# TI1-1-Top.net
KiCad netlist of a schematic drawn in Altium Designer
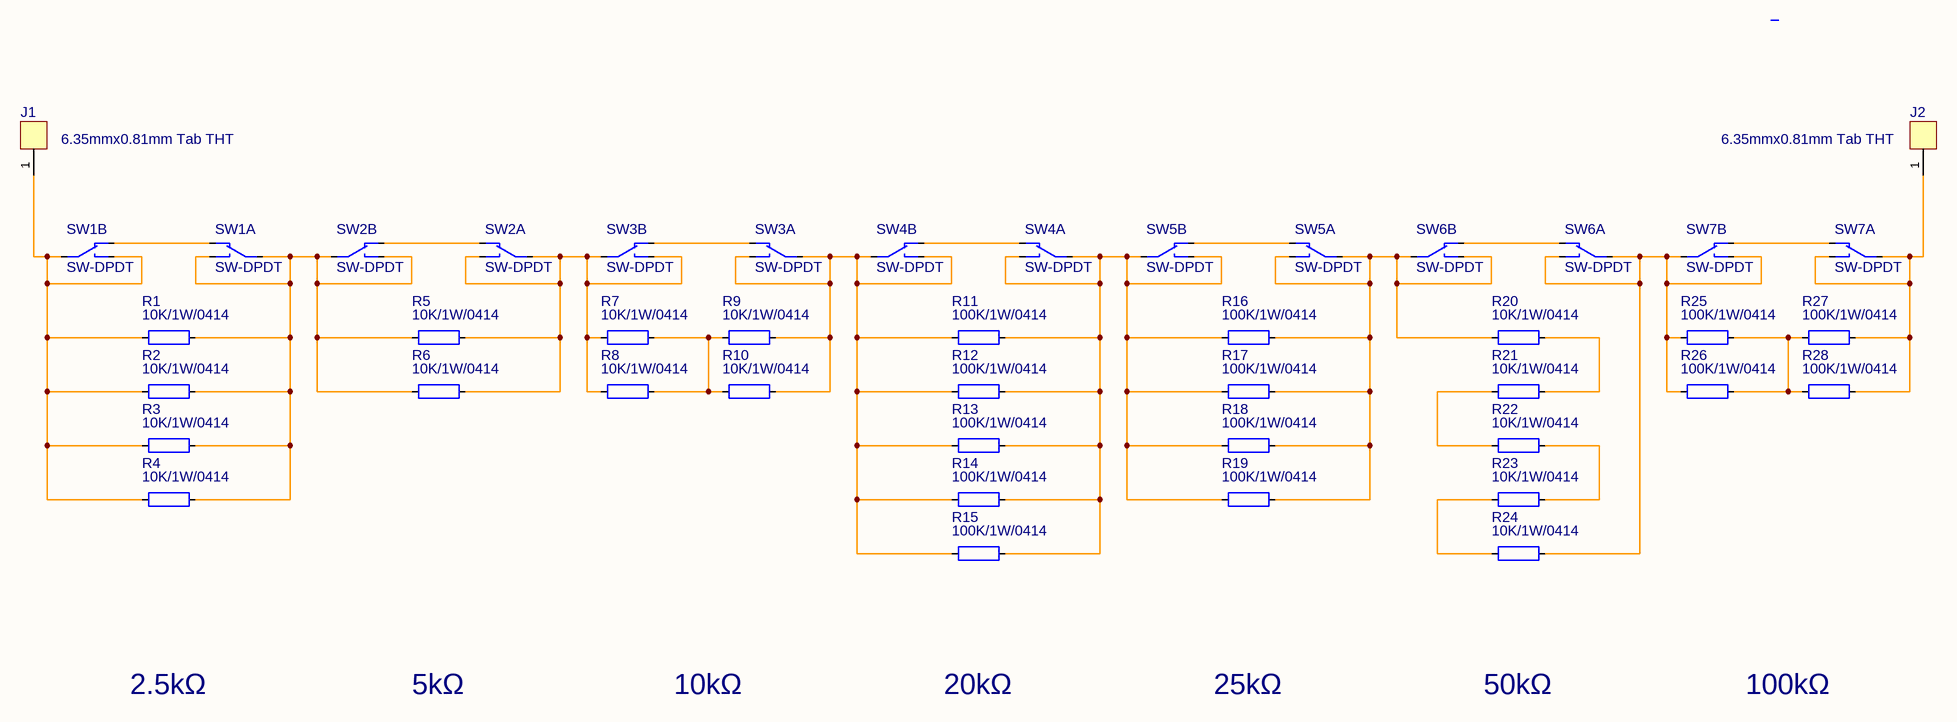
[diagram p0: TI1-1-Top.SchDoc]

(export (version "E")
  (design (tool "Eeschema 10.0.6"))
  (components
    (comp (ref "J1")
      (value "6.35mmx0.81mm Tab THT")
      (footprint "Tab_THT_635")
      (description "CONN QC TAB 0.250 SOLDER")
      (fields (field (name "PART NUMBER") "Tab_025_THT") (field (name "MANUFACTURER") "GENERIC"))
      (libsource (lib "daniw_altium_lib") (part "CON1"))
    )
    (comp (ref "J2")
      (value "6.35mmx0.81mm Tab THT")
      (footprint "Tab_THT_635")
      (description "CONN QC TAB 0.250 SOLDER")
      (fields (field (name "PART NUMBER") "Tab_025_THT") (field (name "MANUFACTURER") "GENERIC"))
      (libsource (lib "daniw_altium_lib") (part "CON1"))
    )
    (comp (ref "R1")
      (value "10K/1W/0414")
      (footprint "RESAD1500W80L1200D400B")
      (description "RES TH 1W 0414 10K")
      (fields (field (name "MANUFACTURER") "GENERIC"))
      (libsource (lib "daniw_altium_lib") (part "R"))
    )
    (comp (ref "R2")
      (value "10K/1W/0414")
      (footprint "RESAD1500W80L1200D400B")
      (description "RES TH 1W 0414 10K")
      (fields (field (name "MANUFACTURER") "GENERIC"))
      (libsource (lib "daniw_altium_lib") (part "R"))
    )
    (comp (ref "R3")
      (value "10K/1W/0414")
      (footprint "RESAD1500W80L1200D400B")
      (description "RES TH 1W 0414 10K")
      (fields (field (name "MANUFACTURER") "GENERIC"))
      (libsource (lib "daniw_altium_lib") (part "R"))
    )
    (comp (ref "R4")
      (value "10K/1W/0414")
      (footprint "RESAD1500W80L1200D400B")
      (description "RES TH 1W 0414 10K")
      (fields (field (name "MANUFACTURER") "GENERIC"))
      (libsource (lib "daniw_altium_lib") (part "R"))
    )
    (comp (ref "R5")
      (value "10K/1W/0414")
      (footprint "RESAD1500W80L1200D400B")
      (description "RES TH 1W 0414 10K")
      (fields (field (name "MANUFACTURER") "GENERIC"))
      (libsource (lib "daniw_altium_lib") (part "R"))
    )
    (comp (ref "R6")
      (value "10K/1W/0414")
      (footprint "RESAD1500W80L1200D400B")
      (description "RES TH 1W 0414 10K")
      (fields (field (name "MANUFACTURER") "GENERIC"))
      (libsource (lib "daniw_altium_lib") (part "R"))
    )
    (comp (ref "R7")
      (value "10K/1W/0414")
      (footprint "RESAD1500W80L1200D400B")
      (description "RES TH 1W 0414 10K")
      (fields (field (name "MANUFACTURER") "GENERIC"))
      (libsource (lib "daniw_altium_lib") (part "R"))
    )
    (comp (ref "R8")
      (value "10K/1W/0414")
      (footprint "RESAD1500W80L1200D400B")
      (description "RES TH 1W 0414 10K")
      (fields (field (name "MANUFACTURER") "GENERIC"))
      (libsource (lib "daniw_altium_lib") (part "R"))
    )
    (comp (ref "R9")
      (value "10K/1W/0414")
      (footprint "RESAD1500W80L1200D400B")
      (description "RES TH 1W 0414 10K")
      (fields (field (name "MANUFACTURER") "GENERIC"))
      (libsource (lib "daniw_altium_lib") (part "R"))
    )
    (comp (ref "R10")
      (value "10K/1W/0414")
      (footprint "RESAD1500W80L1200D400B")
      (description "RES TH 1W 0414 10K")
      (fields (field (name "MANUFACTURER") "GENERIC"))
      (libsource (lib "daniw_altium_lib") (part "R"))
    )
    (comp (ref "R11")
      (value "100K/1W/0414")
      (footprint "RESAD1500W80L1200D400B")
      (description "RES TH 1W 0414 100K")
      (fields (field (name "MANUFACTURER") "GENERIC"))
      (libsource (lib "daniw_altium_lib") (part "R"))
    )
    (comp (ref "R12")
      (value "100K/1W/0414")
      (footprint "RESAD1500W80L1200D400B")
      (description "RES TH 1W 0414 100K")
      (fields (field (name "MANUFACTURER") "GENERIC"))
      (libsource (lib "daniw_altium_lib") (part "R"))
    )
    (comp (ref "R13")
      (value "100K/1W/0414")
      (footprint "RESAD1500W80L1200D400B")
      (description "RES TH 1W 0414 100K")
      (fields (field (name "MANUFACTURER") "GENERIC"))
      (libsource (lib "daniw_altium_lib") (part "R"))
    )
    (comp (ref "R14")
      (value "100K/1W/0414")
      (footprint "RESAD1500W80L1200D400B")
      (description "RES TH 1W 0414 100K")
      (fields (field (name "MANUFACTURER") "GENERIC"))
      (libsource (lib "daniw_altium_lib") (part "R"))
    )
    (comp (ref "R15")
      (value "100K/1W/0414")
      (footprint "RESAD1500W80L1200D400B")
      (description "RES TH 1W 0414 100K")
      (fields (field (name "MANUFACTURER") "GENERIC"))
      (libsource (lib "daniw_altium_lib") (part "R"))
    )
    (comp (ref "R16")
      (value "100K/1W/0414")
      (footprint "RESAD1500W80L1200D400B")
      (description "RES TH 1W 0414 100K")
      (fields (field (name "MANUFACTURER") "GENERIC"))
      (libsource (lib "daniw_altium_lib") (part "R"))
    )
    (comp (ref "R17")
      (value "100K/1W/0414")
      (footprint "RESAD1500W80L1200D400B")
      (description "RES TH 1W 0414 100K")
      (fields (field (name "MANUFACTURER") "GENERIC"))
      (libsource (lib "daniw_altium_lib") (part "R"))
    )
    (comp (ref "R18")
      (value "100K/1W/0414")
      (footprint "RESAD1500W80L1200D400B")
      (description "RES TH 1W 0414 100K")
      (fields (field (name "MANUFACTURER") "GENERIC"))
      (libsource (lib "daniw_altium_lib") (part "R"))
    )
    (comp (ref "R19")
      (value "100K/1W/0414")
      (footprint "RESAD1500W80L1200D400B")
      (description "RES TH 1W 0414 100K")
      (fields (field (name "MANUFACTURER") "GENERIC"))
      (libsource (lib "daniw_altium_lib") (part "R"))
    )
    (comp (ref "R20")
      (value "10K/1W/0414")
      (footprint "RESAD1500W80L1200D400B")
      (description "RES TH 1W 0414 10K")
      (fields (field (name "MANUFACTURER") "GENERIC"))
      (libsource (lib "daniw_altium_lib") (part "R"))
    )
    (comp (ref "R21")
      (value "10K/1W/0414")
      (footprint "RESAD1500W80L1200D400B")
      (description "RES TH 1W 0414 10K")
      (fields (field (name "MANUFACTURER") "GENERIC"))
      (libsource (lib "daniw_altium_lib") (part "R"))
    )
    (comp (ref "R22")
      (value "10K/1W/0414")
      (footprint "RESAD1500W80L1200D400B")
      (description "RES TH 1W 0414 10K")
      (fields (field (name "MANUFACTURER") "GENERIC"))
      (libsource (lib "daniw_altium_lib") (part "R"))
    )
    (comp (ref "R23")
      (value "10K/1W/0414")
      (footprint "RESAD1500W80L1200D400B")
      (description "RES TH 1W 0414 10K")
      (fields (field (name "MANUFACTURER") "GENERIC"))
      (libsource (lib "daniw_altium_lib") (part "R"))
    )
    (comp (ref "R24")
      (value "10K/1W/0414")
      (footprint "RESAD1500W80L1200D400B")
      (description "RES TH 1W 0414 10K")
      (fields (field (name "MANUFACTURER") "GENERIC"))
      (libsource (lib "daniw_altium_lib") (part "R"))
    )
    (comp (ref "R25")
      (value "100K/1W/0414")
      (footprint "RESAD1500W80L1200D400B")
      (description "RES TH 1W 0414 100K")
      (fields (field (name "MANUFACTURER") "GENERIC"))
      (libsource (lib "daniw_altium_lib") (part "R"))
    )
    (comp (ref "R26")
      (value "100K/1W/0414")
      (footprint "RESAD1500W80L1200D400B")
      (description "RES TH 1W 0414 100K")
      (fields (field (name "MANUFACTURER") "GENERIC"))
      (libsource (lib "daniw_altium_lib") (part "R"))
    )
    (comp (ref "R27")
      (value "100K/1W/0414")
      (footprint "RESAD1500W80L1200D400B")
      (description "RES TH 1W 0414 100K")
      (fields (field (name "MANUFACTURER") "GENERIC"))
      (libsource (lib "daniw_altium_lib") (part "R"))
    )
    (comp (ref "R28")
      (value "100K/1W/0414")
      (footprint "RESAD1500W80L1200D400B")
      (description "RES TH 1W 0414 100K")
      (fields (field (name "MANUFACTURER") "GENERIC"))
      (libsource (lib "daniw_altium_lib") (part "R"))
    )
    (comp (ref "SW1")
      (value "SW-DPDT")
      (footprint "RND_DPDT_12.6mm_210-00450")
      (description "Miniature Toggle Switch, ON-ON, DPDT, 2A, IP67")
      (fields (field (name "PART NUMBER") "SW-DPDT-RND-210-00450") (field (name "MANUFACTURER") "RND"))
      (libsource (lib "daniw_altium_lib") (part "SW_DPDT"))
    )
    (comp (ref "SW2")
      (value "SW-DPDT")
      (footprint "RND_DPDT_12.6mm_210-00450")
      (description "Miniature Toggle Switch, ON-ON, DPDT, 2A, IP67")
      (fields (field (name "PART NUMBER") "SW-DPDT-RND-210-00450") (field (name "MANUFACTURER") "RND"))
      (libsource (lib "daniw_altium_lib") (part "SW_DPDT"))
    )
    (comp (ref "SW3")
      (value "SW-DPDT")
      (footprint "RND_DPDT_12.6mm_210-00450")
      (description "Miniature Toggle Switch, ON-ON, DPDT, 2A, IP67")
      (fields (field (name "PART NUMBER") "SW-DPDT-RND-210-00450") (field (name "MANUFACTURER") "RND"))
      (libsource (lib "daniw_altium_lib") (part "SW_DPDT"))
    )
    (comp (ref "SW4")
      (value "SW-DPDT")
      (footprint "RND_DPDT_12.6mm_210-00450")
      (description "Miniature Toggle Switch, ON-ON, DPDT, 2A, IP67")
      (fields (field (name "PART NUMBER") "SW-DPDT-RND-210-00450") (field (name "MANUFACTURER") "RND"))
      (libsource (lib "daniw_altium_lib") (part "SW_DPDT"))
    )
    (comp (ref "SW5")
      (value "SW-DPDT")
      (footprint "RND_DPDT_12.6mm_210-00450")
      (description "Miniature Toggle Switch, ON-ON, DPDT, 2A, IP67")
      (fields (field (name "PART NUMBER") "SW-DPDT-RND-210-00450") (field (name "MANUFACTURER") "RND"))
      (libsource (lib "daniw_altium_lib") (part "SW_DPDT"))
    )
    (comp (ref "SW6")
      (value "SW-DPDT")
      (footprint "RND_DPDT_12.6mm_210-00450")
      (description "Miniature Toggle Switch, ON-ON, DPDT, 2A, IP67")
      (fields (field (name "PART NUMBER") "SW-DPDT-RND-210-00450") (field (name "MANUFACTURER") "RND"))
      (libsource (lib "daniw_altium_lib") (part "SW_DPDT"))
    )
    (comp (ref "SW7")
      (value "SW-DPDT")
      (footprint "RND_DPDT_12.6mm_210-00450")
      (description "Miniature Toggle Switch, ON-ON, DPDT, 2A, IP67")
      (fields (field (name "PART NUMBER") "SW-DPDT-RND-210-00450") (field (name "MANUFACTURER") "RND"))
      (libsource (lib "daniw_altium_lib") (part "SW_DPDT"))
    )
  )
  (nets
    (net (code "1") (name "Net-(R10-Pad2)") (class "Default")
      (node (ref "R10") (pin "2") (pinfunction "2_2") (pintype "passive"))
      (node (ref "R7") (pin "1") (pinfunction "1_1") (pintype "passive"))
      (node (ref "R8") (pin "1") (pinfunction "1_1") (pintype "passive"))
      (node (ref "R9") (pin "2") (pinfunction "2_2") (pintype "passive"))
    )
    (net (code "2") (name "Net-(R20-Pad1)") (class "Default")
      (node (ref "R20") (pin "1") (pinfunction "1_1") (pintype "passive"))
      (node (ref "R21") (pin "1") (pinfunction "1_1") (pintype "passive"))
    )
    (net (code "3") (name "Net-(R21-Pad2)") (class "Default")
      (node (ref "R21") (pin "2") (pinfunction "2_2") (pintype "passive"))
      (node (ref "R22") (pin "2") (pinfunction "2_2") (pintype "passive"))
    )
    (net (code "4") (name "Net-(R22-Pad1)") (class "Default")
      (node (ref "R22") (pin "1") (pinfunction "1_1") (pintype "passive"))
      (node (ref "R23") (pin "1") (pinfunction "1_1") (pintype "passive"))
    )
    (net (code "5") (name "Net-(R23-Pad2)") (class "Default")
      (node (ref "R23") (pin "2") (pinfunction "2_2") (pintype "passive"))
      (node (ref "R24") (pin "2") (pinfunction "2_2") (pintype "passive"))
    )
    (net (code "6") (name "Net-(R25-Pad1)") (class "Default")
      (node (ref "R25") (pin "1") (pinfunction "1_1") (pintype "passive"))
      (node (ref "R26") (pin "1") (pinfunction "1_1") (pintype "passive"))
      (node (ref "R27") (pin "2") (pinfunction "2_2") (pintype "passive"))
      (node (ref "R28") (pin "2") (pinfunction "2_2") (pintype "passive"))
    )
    (net (code "7") (name "Net-(SW1A-COM1)") (class "Default")
      (node (ref "R1") (pin "1") (pinfunction "1_1") (pintype "passive"))
      (node (ref "R2") (pin "1") (pinfunction "1_1") (pintype "passive"))
      (node (ref "R3") (pin "1") (pinfunction "1_1") (pintype "passive"))
      (node (ref "R4") (pin "1") (pinfunction "1_1") (pintype "passive"))
      (node (ref "R5") (pin "2") (pinfunction "2_2") (pintype "passive"))
      (node (ref "R6") (pin "2") (pinfunction "2_2") (pintype "passive"))
      (node (ref "SW1") (pin "1") (pinfunction "COM1_1") (pintype "passive"))
      (node (ref "SW1") (pin "3") (pinfunction "NO1_3") (pintype "passive"))
      (node (ref "SW2") (pin "4") (pinfunction "COM2_4") (pintype "passive"))
      (node (ref "SW2") (pin "6") (pinfunction "NO2_6") (pintype "passive"))
    )
    (net (code "8") (name "Net-(SW1A-NC1)") (class "Default")
      (node (ref "SW1") (pin "2") (pinfunction "NC1_2") (pintype "passive"))
      (node (ref "SW1") (pin "5") (pinfunction "NC2_5") (pintype "passive"))
    )
    (net (code "9") (name "Net-(SW1B-COM2)") (class "Default")
      (node (ref "J1") (pin "1") (pintype "passive"))
      (node (ref "R1") (pin "2") (pinfunction "2_2") (pintype "passive"))
      (node (ref "R2") (pin "2") (pinfunction "2_2") (pintype "passive"))
      (node (ref "R3") (pin "2") (pinfunction "2_2") (pintype "passive"))
      (node (ref "R4") (pin "2") (pinfunction "2_2") (pintype "passive"))
      (node (ref "SW1") (pin "4") (pinfunction "COM2_4") (pintype "passive"))
      (node (ref "SW1") (pin "6") (pinfunction "NO2_6") (pintype "passive"))
    )
    (net (code "10") (name "Net-(SW2A-COM1)") (class "Default")
      (node (ref "R5") (pin "1") (pinfunction "1_1") (pintype "passive"))
      (node (ref "R6") (pin "1") (pinfunction "1_1") (pintype "passive"))
      (node (ref "R7") (pin "2") (pinfunction "2_2") (pintype "passive"))
      (node (ref "R8") (pin "2") (pinfunction "2_2") (pintype "passive"))
      (node (ref "SW2") (pin "1") (pinfunction "COM1_1") (pintype "passive"))
      (node (ref "SW2") (pin "3") (pinfunction "NO1_3") (pintype "passive"))
      (node (ref "SW3") (pin "4") (pinfunction "COM2_4") (pintype "passive"))
      (node (ref "SW3") (pin "6") (pinfunction "NO2_6") (pintype "passive"))
    )
    (net (code "11") (name "Net-(SW2A-NC1)") (class "Default")
      (node (ref "SW2") (pin "2") (pinfunction "NC1_2") (pintype "passive"))
      (node (ref "SW2") (pin "5") (pinfunction "NC2_5") (pintype "passive"))
    )
    (net (code "12") (name "Net-(SW3A-COM1)") (class "Default")
      (node (ref "R10") (pin "1") (pinfunction "1_1") (pintype "passive"))
      (node (ref "R11") (pin "2") (pinfunction "2_2") (pintype "passive"))
      (node (ref "R12") (pin "2") (pinfunction "2_2") (pintype "passive"))
      (node (ref "R13") (pin "2") (pinfunction "2_2") (pintype "passive"))
      (node (ref "R14") (pin "2") (pinfunction "2_2") (pintype "passive"))
      (node (ref "R15") (pin "2") (pinfunction "2_2") (pintype "passive"))
      (node (ref "R9") (pin "1") (pinfunction "1_1") (pintype "passive"))
      (node (ref "SW3") (pin "1") (pinfunction "COM1_1") (pintype "passive"))
      (node (ref "SW3") (pin "3") (pinfunction "NO1_3") (pintype "passive"))
      (node (ref "SW4") (pin "4") (pinfunction "COM2_4") (pintype "passive"))
      (node (ref "SW4") (pin "6") (pinfunction "NO2_6") (pintype "passive"))
    )
    (net (code "13") (name "Net-(SW3A-NC1)") (class "Default")
      (node (ref "SW3") (pin "2") (pinfunction "NC1_2") (pintype "passive"))
      (node (ref "SW3") (pin "5") (pinfunction "NC2_5") (pintype "passive"))
    )
    (net (code "14") (name "Net-(SW4A-COM1)") (class "Default")
      (node (ref "R11") (pin "1") (pinfunction "1_1") (pintype "passive"))
      (node (ref "R12") (pin "1") (pinfunction "1_1") (pintype "passive"))
      (node (ref "R13") (pin "1") (pinfunction "1_1") (pintype "passive"))
      (node (ref "R14") (pin "1") (pinfunction "1_1") (pintype "passive"))
      (node (ref "R15") (pin "1") (pinfunction "1_1") (pintype "passive"))
      (node (ref "R16") (pin "2") (pinfunction "2_2") (pintype "passive"))
      (node (ref "R17") (pin "2") (pinfunction "2_2") (pintype "passive"))
      (node (ref "R18") (pin "2") (pinfunction "2_2") (pintype "passive"))
      (node (ref "R19") (pin "2") (pinfunction "2_2") (pintype "passive"))
      (node (ref "SW4") (pin "1") (pinfunction "COM1_1") (pintype "passive"))
      (node (ref "SW4") (pin "3") (pinfunction "NO1_3") (pintype "passive"))
      (node (ref "SW5") (pin "4") (pinfunction "COM2_4") (pintype "passive"))
      (node (ref "SW5") (pin "6") (pinfunction "NO2_6") (pintype "passive"))
    )
    (net (code "15") (name "Net-(SW4A-NC1)") (class "Default")
      (node (ref "SW4") (pin "2") (pinfunction "NC1_2") (pintype "passive"))
      (node (ref "SW4") (pin "5") (pinfunction "NC2_5") (pintype "passive"))
    )
    (net (code "16") (name "Net-(SW5A-COM1)") (class "Default")
      (node (ref "R16") (pin "1") (pinfunction "1_1") (pintype "passive"))
      (node (ref "R17") (pin "1") (pinfunction "1_1") (pintype "passive"))
      (node (ref "R18") (pin "1") (pinfunction "1_1") (pintype "passive"))
      (node (ref "R19") (pin "1") (pinfunction "1_1") (pintype "passive"))
      (node (ref "R20") (pin "2") (pinfunction "2_2") (pintype "passive"))
      (node (ref "SW5") (pin "1") (pinfunction "COM1_1") (pintype "passive"))
      (node (ref "SW5") (pin "3") (pinfunction "NO1_3") (pintype "passive"))
      (node (ref "SW6") (pin "4") (pinfunction "COM2_4") (pintype "passive"))
      (node (ref "SW6") (pin "6") (pinfunction "NO2_6") (pintype "passive"))
    )
    (net (code "17") (name "Net-(SW5A-NC1)") (class "Default")
      (node (ref "SW5") (pin "2") (pinfunction "NC1_2") (pintype "passive"))
      (node (ref "SW5") (pin "5") (pinfunction "NC2_5") (pintype "passive"))
    )
    (net (code "18") (name "Net-(SW6A-COM1)") (class "Default")
      (node (ref "R24") (pin "1") (pinfunction "1_1") (pintype "passive"))
      (node (ref "R25") (pin "2") (pinfunction "2_2") (pintype "passive"))
      (node (ref "R26") (pin "2") (pinfunction "2_2") (pintype "passive"))
      (node (ref "SW6") (pin "1") (pinfunction "COM1_1") (pintype "passive"))
      (node (ref "SW6") (pin "3") (pinfunction "NO1_3") (pintype "passive"))
      (node (ref "SW7") (pin "4") (pinfunction "COM2_4") (pintype "passive"))
      (node (ref "SW7") (pin "6") (pinfunction "NO2_6") (pintype "passive"))
    )
    (net (code "19") (name "Net-(SW6A-NC1)") (class "Default")
      (node (ref "SW6") (pin "2") (pinfunction "NC1_2") (pintype "passive"))
      (node (ref "SW6") (pin "5") (pinfunction "NC2_5") (pintype "passive"))
    )
    (net (code "20") (name "Net-(SW7A-COM1)") (class "Default")
      (node (ref "J2") (pin "1") (pintype "passive"))
      (node (ref "R27") (pin "1") (pinfunction "1_1") (pintype "passive"))
      (node (ref "R28") (pin "1") (pinfunction "1_1") (pintype "passive"))
      (node (ref "SW7") (pin "1") (pinfunction "COM1_1") (pintype "passive"))
      (node (ref "SW7") (pin "3") (pinfunction "NO1_3") (pintype "passive"))
    )
    (net (code "21") (name "Net-(SW7A-NC1)") (class "Default")
      (node (ref "SW7") (pin "2") (pinfunction "NC1_2") (pintype "passive"))
      (node (ref "SW7") (pin "5") (pinfunction "NC2_5") (pintype "passive"))
    )
  )
)
